# mrShark_06.net
KiCad netlist of a schematic drawn in EAGLE
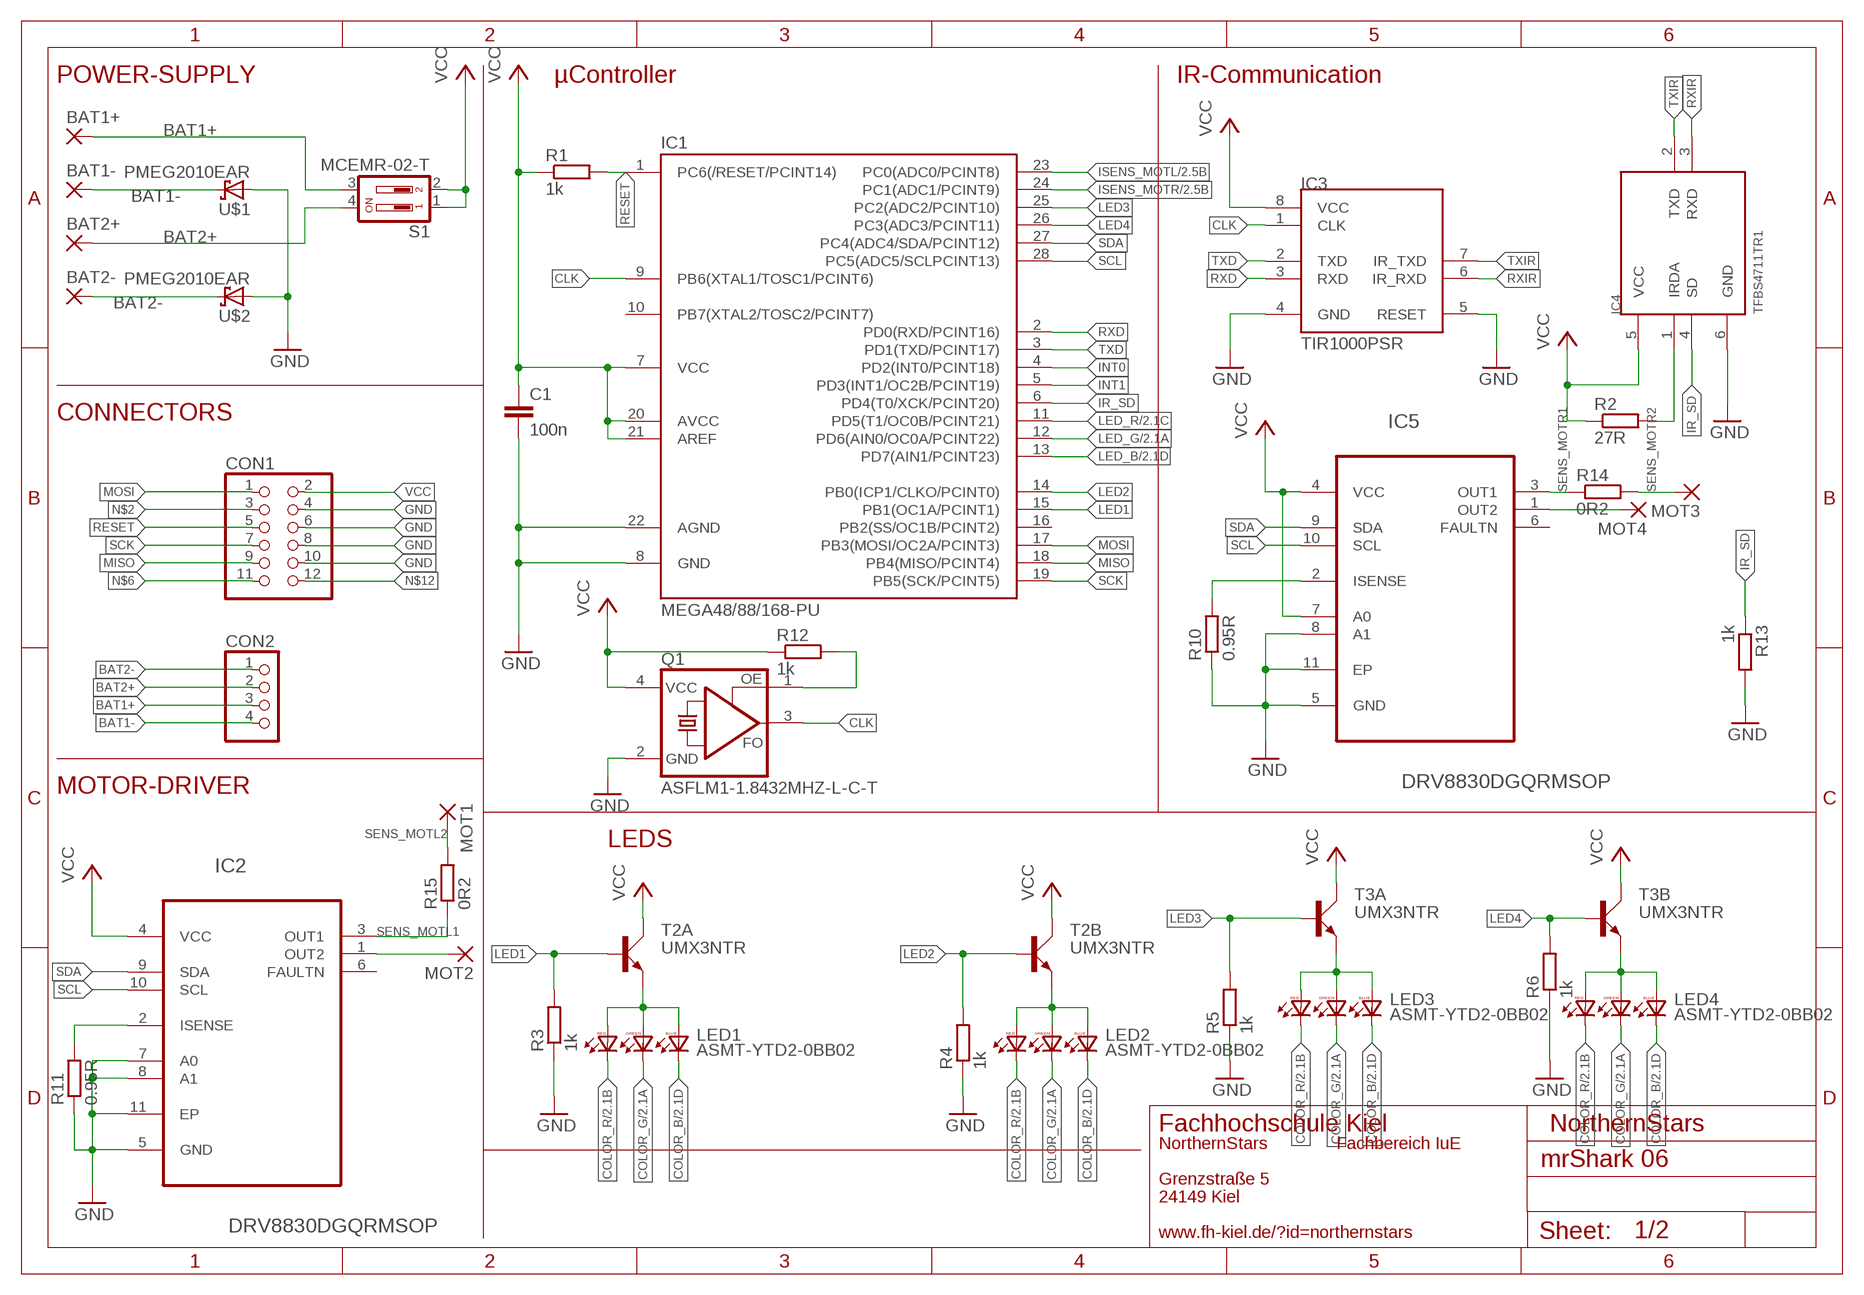
[diagram p0: schematic, sheet 1]
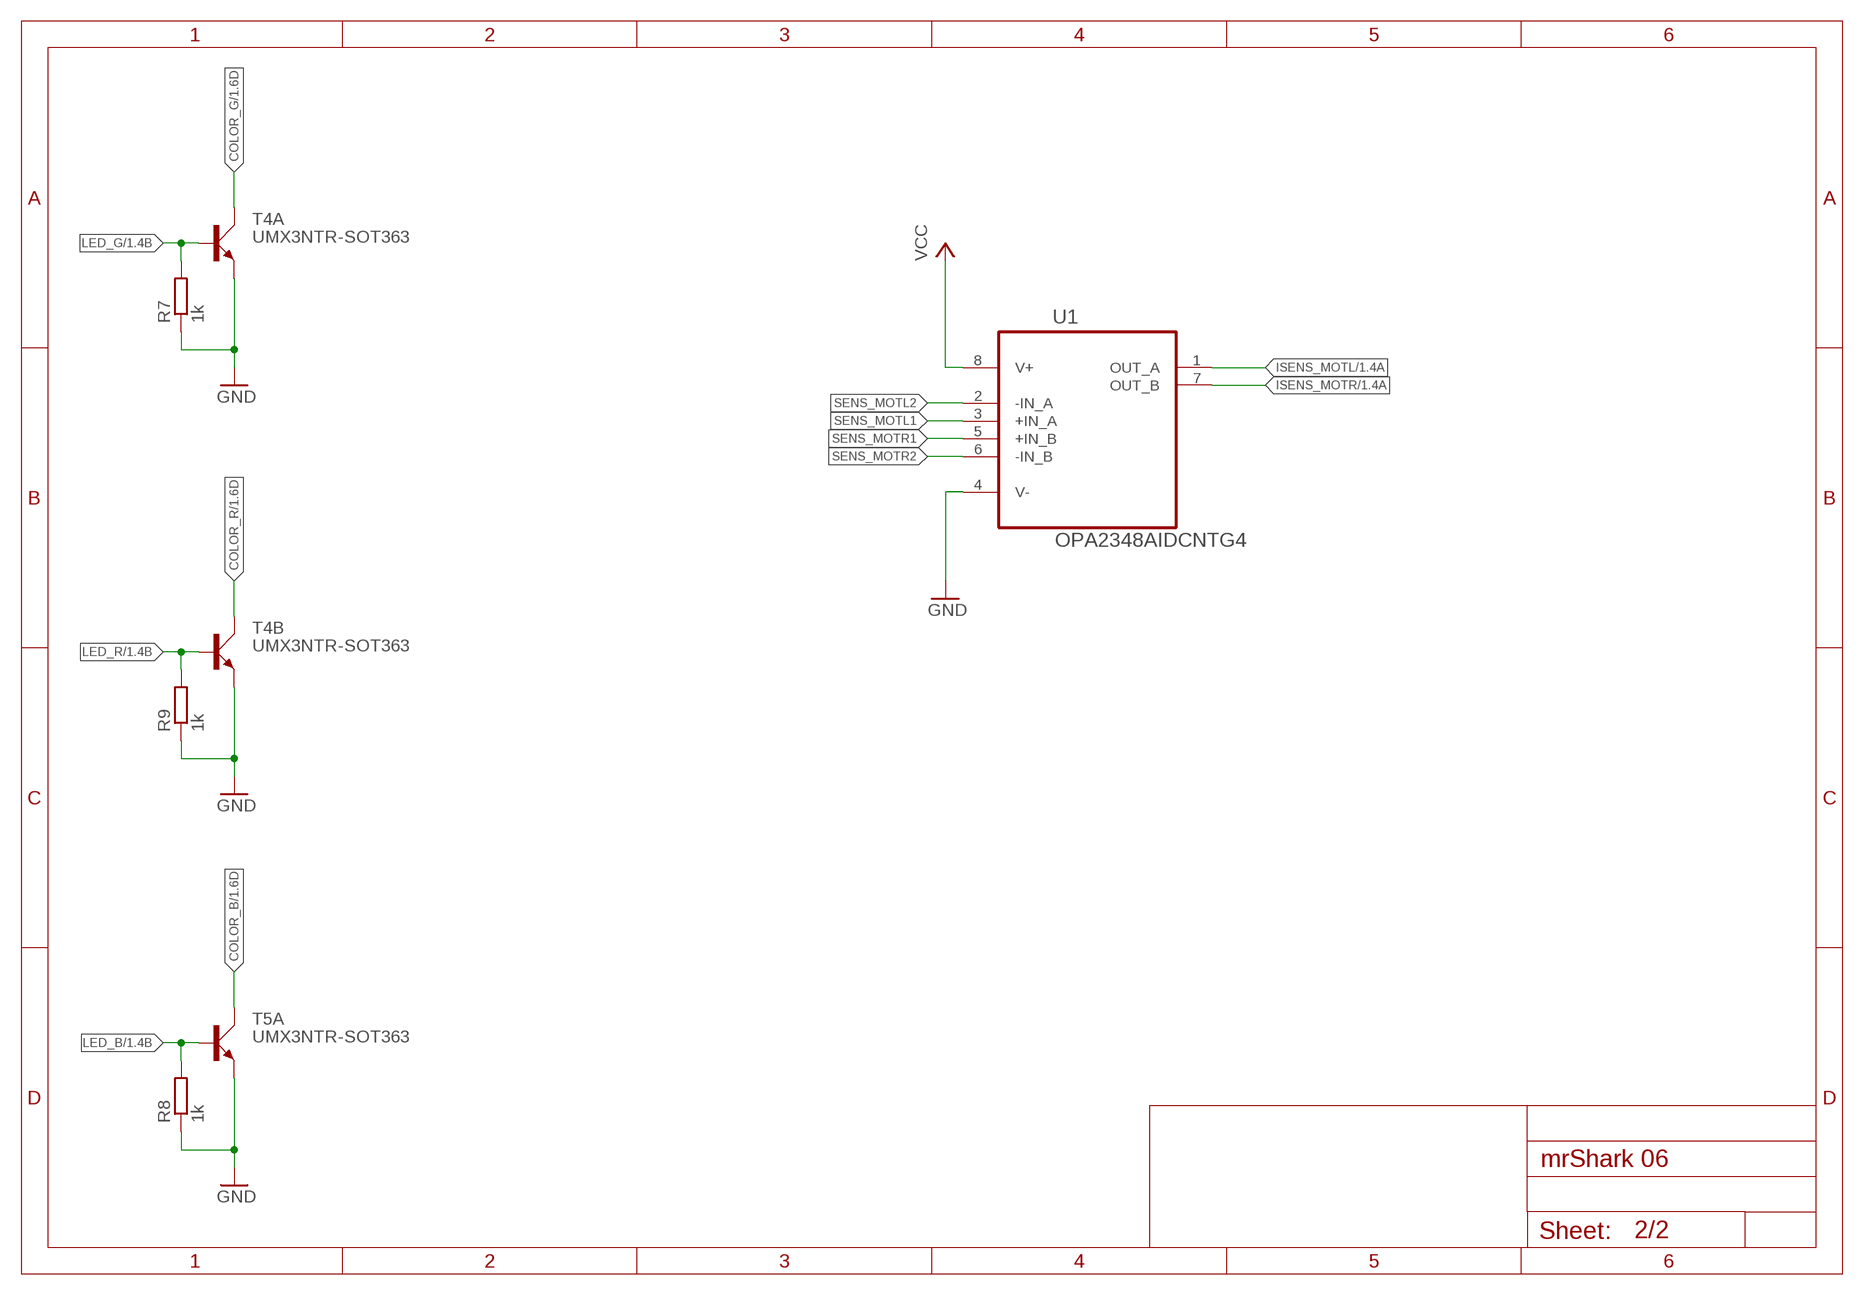
[diagram p1: schematic, sheet 2]

(export (version "E")
  (design (tool "Eeschema 10.0.6"))
  (components
    (comp (ref "R7")
      (value "1k")
      (footprint "eagle-import:R1206")
      (libsource (lib "eagle-import") (part "R-EU_R1206"))
    )
    (comp (ref "R8")
      (value "1k")
      (footprint "eagle-import:R1206")
      (libsource (lib "eagle-import") (part "R-EU_R1206"))
    )
    (comp (ref "R9")
      (value "1k")
      (footprint "eagle-import:R1206")
      (libsource (lib "eagle-import") (part "R-EU_R1206"))
    )
    (comp (ref "T4")
      (value "UMX3NTR-SOT363")
      (footprint "eagle-import:SOT363_INFINEON")
      (libsource (lib "eagle-import") (part "UMX3NTR-SOT363"))
    )
    (comp (ref "T5")
      (value "UMX3NTR-SOT363")
      (footprint "eagle-import:SOT363_INFINEON")
      (libsource (lib "eagle-import") (part "UMX3NTR-SOT363"))
    )
    (comp (ref "U1")
      (value "OPA2348AIDCNTG4")
      (footprint "eagle-import:SOT65P280X145-8N")
      (libsource (lib "eagle-import") (part "OPA2348AIDCNTG4"))
    )
    (comp (ref "BAT1+")
      (value "1,6/0,9")
      (footprint "eagle-import:1,6_0,9")
      (libsource (lib "eagle-import") (part "1,6/0,9"))
    )
    (comp (ref "BAT1-")
      (value "1,6/0,9")
      (footprint "eagle-import:1,6_0,9")
      (libsource (lib "eagle-import") (part "1,6/0,9"))
    )
    (comp (ref "BAT2+")
      (value "1,6/0,9")
      (footprint "eagle-import:1,6_0,9")
      (libsource (lib "eagle-import") (part "1,6/0,9"))
    )
    (comp (ref "BAT2-")
      (value "1,6/0,9")
      (footprint "eagle-import:1,6_0,9")
      (libsource (lib "eagle-import") (part "1,6/0,9"))
    )
    (comp (ref "C1")
      (value "100n")
      (footprint "eagle-import:C1206")
      (libsource (lib "eagle-import") (part "C-EUC1206"))
    )
    (comp (ref "CON1")
      (value "PINHD-2X06_2.54-SMD")
      (footprint "eagle-import:2X06SMD")
      (libsource (lib "eagle-import") (part "PINHD-2X06_2.54-SMD"))
    )
    (comp (ref "CON2")
      (value "PINHD-1X04_2.54-SMD-90°")
      (footprint "eagle-import:1X04SMD_90")
      (libsource (lib "eagle-import") (part "PINHD-1X04_2.54-SMD-90°"))
    )
    (comp (ref "IC1")
      (value "MEGA48/88/168-PU")
      (footprint "eagle-import:DIL28-3")
      (libsource (lib "eagle-import") (part "MEGA48/88/168-PU"))
    )
    (comp (ref "IC2")
      (value "DRV8830DGQRMSOP")
      (footprint "eagle-import:SOP65P640X110-15N")
      (fields (field (name "MPN") "DRV8830DGQR"))
      (libsource (lib "eagle-import") (part "DRV8830DGQRMSOP"))
    )
    (comp (ref "IC3")
      (value "TIR1000PSR")
      (footprint "eagle-import:SO-08")
      (libsource (lib "eagle-import") (part "TIR1000PSR"))
    )
    (comp (ref "IC4")
      (value "TFBS4711TR1")
      (footprint "eagle-import:TFBS4711")
      (libsource (lib "eagle-import") (part "TFBS4711TR1"))
    )
    (comp (ref "IC5")
      (value "DRV8830DGQRMSOP")
      (footprint "eagle-import:SOP65P640X110-15N")
      (fields (field (name "MPN") "DRV8830DGQR"))
      (libsource (lib "eagle-import") (part "DRV8830DGQRMSOP"))
    )
    (comp (ref "LED1")
      (value "ASMT-YTD2-0BB02")
      (footprint "eagle-import:PLCC6K")
      (libsource (lib "eagle-import") (part "PLCC6K"))
    )
    (comp (ref "LED2")
      (value "ASMT-YTD2-0BB02")
      (footprint "eagle-import:PLCC6K")
      (libsource (lib "eagle-import") (part "PLCC6K"))
    )
    (comp (ref "LED3")
      (value "ASMT-YTD2-0BB02")
      (footprint "eagle-import:PLCC6K")
      (libsource (lib "eagle-import") (part "PLCC6K"))
    )
    (comp (ref "LED4")
      (value "ASMT-YTD2-0BB02")
      (footprint "eagle-import:PLCC6K")
      (libsource (lib "eagle-import") (part "PLCC6K"))
    )
    (comp (ref "MOT1")
      (value "1,6/0,9")
      (footprint "eagle-import:1,6_0,9")
      (libsource (lib "eagle-import") (part "1,6/0,9"))
    )
    (comp (ref "MOT2")
      (value "1,6/0,9")
      (footprint "eagle-import:1,6_0,9")
      (libsource (lib "eagle-import") (part "1,6/0,9"))
    )
    (comp (ref "MOT3")
      (value "1,6/0,9")
      (footprint "eagle-import:1,6_0,9")
      (libsource (lib "eagle-import") (part "1,6/0,9"))
    )
    (comp (ref "MOT4")
      (value "1,6/0,9")
      (footprint "eagle-import:1,6_0,9")
      (libsource (lib "eagle-import") (part "1,6/0,9"))
    )
    (comp (ref "Q1")
      (value "ASFLM1-1.8432MHZ-L-C-T")
      (footprint "eagle-import:HC536")
      (libsource (lib "eagle-import") (part "HC536R"))
    )
    (comp (ref "R1")
      (value "1k")
      (footprint "eagle-import:R1206")
      (libsource (lib "eagle-import") (part "R-EU_R1206"))
    )
    (comp (ref "R2")
      (value "27R")
      (footprint "eagle-import:R1206")
      (libsource (lib "eagle-import") (part "R-EU_R1206"))
    )
    (comp (ref "R3")
      (value "1k")
      (footprint "eagle-import:R1206")
      (libsource (lib "eagle-import") (part "R-EU_R1206"))
    )
    (comp (ref "R4")
      (value "1k")
      (footprint "eagle-import:R1206")
      (libsource (lib "eagle-import") (part "R-EU_R1206"))
    )
    (comp (ref "R5")
      (value "1k")
      (footprint "eagle-import:R1206")
      (libsource (lib "eagle-import") (part "R-EU_R1206"))
    )
    (comp (ref "R6")
      (value "1k")
      (footprint "eagle-import:R1206")
      (libsource (lib "eagle-import") (part "R-EU_R1206"))
    )
    (comp (ref "R10")
      (value "0.95R")
      (footprint "eagle-import:R1206")
      (libsource (lib "eagle-import") (part "R-EU_R1206"))
    )
    (comp (ref "R11")
      (value "0.95R")
      (footprint "eagle-import:R1206")
      (libsource (lib "eagle-import") (part "R-EU_R1206"))
    )
    (comp (ref "R12")
      (value "1k")
      (footprint "eagle-import:R1206")
      (libsource (lib "eagle-import") (part "R-EU_R1206"))
    )
    (comp (ref "R13")
      (value "1k")
      (footprint "eagle-import:R1206")
      (libsource (lib "eagle-import") (part "R-EU_R1206"))
    )
    (comp (ref "R14")
      (value "0R2")
      (footprint "eagle-import:R0805")
      (libsource (lib "eagle-import") (part "R-EU_R0805"))
    )
    (comp (ref "R15")
      (value "0R2")
      (footprint "eagle-import:R0805")
      (libsource (lib "eagle-import") (part "R-EU_R0805"))
    )
    (comp (ref "S1")
      (value "MCEMR-02-T")
      (footprint "eagle-import:CTS-219-02")
      (libsource (lib "eagle-import") (part "219-02"))
    )
    (comp (ref "T2")
      (value "UMX3NTR")
      (footprint "eagle-import:SOT363_INFINEON")
      (libsource (lib "eagle-import") (part "UMX3NTR-SOT363"))
    )
    (comp (ref "T3")
      (value "UMX3NTR")
      (footprint "eagle-import:SOT363_INFINEON")
      (libsource (lib "eagle-import") (part "UMX3NTR-SOT363"))
    )
    (comp (ref "U$1")
      (value "PMEG2010EAR")
      (footprint "eagle-import:SOD323-R")
      (libsource (lib "eagle-import") (part "PMEG2010EAR"))
    )
    (comp (ref "U$2")
      (value "PMEG2010EAR")
      (footprint "eagle-import:SOD323-R")
      (libsource (lib "eagle-import") (part "PMEG2010EAR"))
    )
  )
  (nets
    (net (code "1") (name "BAT1+") (class "Default")
      (node (ref "BAT1+") (pin "1") (pinfunction "P_1") (pintype "passive"))
      (node (ref "CON2") (pin "3") (pinfunction "3_3") (pintype "passive"))
      (node (ref "S1") (pin "3") (pinfunction "3_3") (pintype "passive"))
    )
    (net (code "2") (name "BAT1-") (class "Default")
      (node (ref "BAT1-") (pin "1") (pinfunction "P_1") (pintype "passive"))
      (node (ref "CON2") (pin "4") (pinfunction "4_4") (pintype "passive"))
      (node (ref "U$1") (pin "C") (pinfunction "C_C") (pintype "passive"))
    )
    (net (code "3") (name "BAT2+") (class "Default")
      (node (ref "BAT2+") (pin "1") (pinfunction "P_1") (pintype "passive"))
      (node (ref "CON2") (pin "2") (pinfunction "2_2") (pintype "passive"))
      (node (ref "S1") (pin "4") (pinfunction "4_4") (pintype "passive"))
    )
    (net (code "4") (name "BAT2-") (class "Default")
      (node (ref "BAT2-") (pin "1") (pinfunction "P_1") (pintype "passive"))
      (node (ref "CON2") (pin "1") (pinfunction "1_1") (pintype "passive"))
      (node (ref "U$2") (pin "C") (pinfunction "C_C") (pintype "passive"))
    )
    (net (code "5") (name "CLK") (class "Default")
      (node (ref "IC1") (pin "9") (pinfunction "PB6(XTAL1/TOSC1/PCINT6)_9") (pintype "bidirectional"))
      (node (ref "IC3") (pin "1") (pinfunction "CLK_1") (pintype "bidirectional"))
      (node (ref "Q1") (pin "3") (pinfunction "FO_3") (pintype "output"))
    )
    (net (code "6") (name "COLOR_B") (class "Default")
      (node (ref "LED1") (pin "1") (pinfunction "BC_1") (pintype "passive"))
      (node (ref "LED2") (pin "1") (pinfunction "BC_1") (pintype "passive"))
      (node (ref "LED3") (pin "1") (pinfunction "BC_1") (pintype "passive"))
      (node (ref "LED4") (pin "1") (pinfunction "BC_1") (pintype "passive"))
      (node (ref "T5") (pin "6") (pinfunction "C_6") (pintype "passive"))
    )
    (net (code "7") (name "COLOR_G") (class "Default")
      (node (ref "LED1") (pin "2") (pinfunction "GC_2") (pintype "passive"))
      (node (ref "LED2") (pin "2") (pinfunction "GC_2") (pintype "passive"))
      (node (ref "LED3") (pin "2") (pinfunction "GC_2") (pintype "passive"))
      (node (ref "LED4") (pin "2") (pinfunction "GC_2") (pintype "passive"))
      (node (ref "T4") (pin "6") (pinfunction "C_6") (pintype "passive"))
    )
    (net (code "8") (name "COLOR_R") (class "Default")
      (node (ref "LED1") (pin "3") (pinfunction "RC_3") (pintype "passive"))
      (node (ref "LED2") (pin "3") (pinfunction "RC_3") (pintype "passive"))
      (node (ref "LED3") (pin "3") (pinfunction "RC_3") (pintype "passive"))
      (node (ref "LED4") (pin "3") (pinfunction "RC_3") (pintype "passive"))
      (node (ref "T4") (pin "4") (pinfunction "C_4") (pintype "passive"))
    )
    (net (code "9") (name "GND") (class "Default")
      (node (ref "C1") (pin "2") (pinfunction "2_2") (pintype "passive"))
      (node (ref "CON1") (pin "10") (pinfunction "10_10") (pintype "passive"))
      (node (ref "CON1") (pin "4") (pinfunction "4_4") (pintype "passive"))
      (node (ref "CON1") (pin "6") (pinfunction "6_6") (pintype "passive"))
      (node (ref "CON1") (pin "8") (pinfunction "8_8") (pintype "passive"))
      (node (ref "IC1") (pin "22") (pinfunction "AGND_22") (pintype "power_in"))
      (node (ref "IC1") (pin "8") (pinfunction "GND_8") (pintype "power_in"))
      (node (ref "IC2") (pin "11") (pinfunction "EP_11") (pintype "passive"))
      (node (ref "IC2") (pin "5") (pinfunction "GND_5") (pintype "passive"))
      (node (ref "IC2") (pin "7") (pinfunction "A0_7") (pintype "input"))
      (node (ref "IC2") (pin "8") (pinfunction "A1_8") (pintype "input"))
      (node (ref "IC3") (pin "4") (pinfunction "GND_4") (pintype "bidirectional"))
      (node (ref "IC3") (pin "5") (pinfunction "RESET_5") (pintype "bidirectional"))
      (node (ref "IC4") (pin "6") (pinfunction "GND_6") (pintype "bidirectional"))
      (node (ref "IC5") (pin "11") (pinfunction "EP_11") (pintype "passive"))
      (node (ref "IC5") (pin "5") (pinfunction "GND_5") (pintype "passive"))
      (node (ref "IC5") (pin "8") (pinfunction "A1_8") (pintype "input"))
      (node (ref "Q1") (pin "2") (pinfunction "GND_2") (pintype "power_in"))
      (node (ref "R10") (pin "1") (pinfunction "1_1") (pintype "passive"))
      (node (ref "R11") (pin "1") (pinfunction "1_1") (pintype "passive"))
      (node (ref "R13") (pin "2") (pinfunction "2_2") (pintype "passive"))
      (node (ref "R3") (pin "1") (pinfunction "1_1") (pintype "passive"))
      (node (ref "R4") (pin "1") (pinfunction "1_1") (pintype "passive"))
      (node (ref "R5") (pin "1") (pinfunction "1_1") (pintype "passive"))
      (node (ref "R6") (pin "1") (pinfunction "1_1") (pintype "passive"))
      (node (ref "R7") (pin "1") (pinfunction "1_1") (pintype "passive"))
      (node (ref "R8") (pin "1") (pinfunction "1_1") (pintype "passive"))
      (node (ref "R9") (pin "1") (pinfunction "1_1") (pintype "passive"))
      (node (ref "T4") (pin "1") (pinfunction "E_1") (pintype "passive"))
      (node (ref "T4") (pin "5") (pinfunction "E_5") (pintype "passive"))
      (node (ref "T5") (pin "1") (pinfunction "E_1") (pintype "passive"))
      (node (ref "U$1") (pin "A") (pinfunction "A_A") (pintype "passive"))
      (node (ref "U$2") (pin "A") (pinfunction "A_A") (pintype "passive"))
      (node (ref "U1") (pin "4") (pinfunction "V-_4") (pintype "power_in"))
    )
    (net (code "10") (name "INT0") (class "Default")
      (node (ref "IC1") (pin "4") (pinfunction "PD2(INT0/PCINT18)_4") (pintype "bidirectional"))
    )
    (net (code "11") (name "INT1") (class "Default")
      (node (ref "IC1") (pin "5") (pinfunction "PD3(INT1/OC2B/PCINT19)_5") (pintype "bidirectional"))
    )
    (net (code "12") (name "IR_SD") (class "Default")
      (node (ref "IC1") (pin "6") (pinfunction "PD4(T0/XCK/PCINT20)_6") (pintype "bidirectional"))
      (node (ref "IC4") (pin "4") (pinfunction "SD_4") (pintype "bidirectional"))
      (node (ref "R13") (pin "1") (pinfunction "1_1") (pintype "passive"))
    )
    (net (code "13") (name "ISENS_MOTL") (class "Default")
      (node (ref "IC1") (pin "23") (pinfunction "PC0(ADC0/PCINT8)_23") (pintype "bidirectional"))
      (node (ref "U1") (pin "1") (pinfunction "OUT_A_1") (pintype "output"))
    )
    (net (code "14") (name "ISENS_MOTR") (class "Default")
      (node (ref "IC1") (pin "24") (pinfunction "PC1(ADC1/PCINT9)_24") (pintype "bidirectional"))
      (node (ref "U1") (pin "7") (pinfunction "OUT_B_7") (pintype "output"))
    )
    (net (code "15") (name "LED1") (class "Default")
      (node (ref "IC1") (pin "15") (pinfunction "PB1(OC1A/PCINT1)_15") (pintype "bidirectional"))
      (node (ref "R3") (pin "2") (pinfunction "2_2") (pintype "passive"))
      (node (ref "T2") (pin "2") (pinfunction "B_2") (pintype "passive"))
    )
    (net (code "16") (name "LED2") (class "Default")
      (node (ref "IC1") (pin "14") (pinfunction "PB0(ICP1/CLKO/PCINT0)_14") (pintype "bidirectional"))
      (node (ref "R4") (pin "2") (pinfunction "2_2") (pintype "passive"))
      (node (ref "T2") (pin "3") (pinfunction "B_3") (pintype "passive"))
    )
    (net (code "17") (name "LED3") (class "Default")
      (node (ref "IC1") (pin "25") (pinfunction "PC2(ADC2/PCINT10)_25") (pintype "bidirectional"))
      (node (ref "R5") (pin "2") (pinfunction "2_2") (pintype "passive"))
      (node (ref "T3") (pin "2") (pinfunction "B_2") (pintype "passive"))
    )
    (net (code "18") (name "LED4") (class "Default")
      (node (ref "IC1") (pin "26") (pinfunction "PC3(ADC3/PCINT11)_26") (pintype "bidirectional"))
      (node (ref "R6") (pin "2") (pinfunction "2_2") (pintype "passive"))
      (node (ref "T3") (pin "3") (pinfunction "B_3") (pintype "passive"))
    )
    (net (code "19") (name "LED_B") (class "Default")
      (node (ref "IC1") (pin "13") (pinfunction "PD7(AIN1/PCINT23)_13") (pintype "bidirectional"))
      (node (ref "R8") (pin "2") (pinfunction "2_2") (pintype "passive"))
      (node (ref "T5") (pin "2") (pinfunction "B_2") (pintype "passive"))
    )
    (net (code "20") (name "LED_G") (class "Default")
      (node (ref "IC1") (pin "12") (pinfunction "PD6(AIN0/OC0A/PCINT22)_12") (pintype "bidirectional"))
      (node (ref "R7") (pin "2") (pinfunction "2_2") (pintype "passive"))
      (node (ref "T4") (pin "2") (pinfunction "B_2") (pintype "passive"))
    )
    (net (code "21") (name "LED_R") (class "Default")
      (node (ref "IC1") (pin "11") (pinfunction "PD5(T1/OC0B/PCINT21)_11") (pintype "bidirectional"))
      (node (ref "R9") (pin "2") (pinfunction "2_2") (pintype "passive"))
      (node (ref "T4") (pin "3") (pinfunction "B_3") (pintype "passive"))
    )
    (net (code "22") (name "MISO") (class "Default")
      (node (ref "CON1") (pin "9") (pinfunction "9_9") (pintype "passive"))
      (node (ref "IC1") (pin "18") (pinfunction "PB4(MISO/PCINT4)_18") (pintype "bidirectional"))
    )
    (net (code "23") (name "MOSI") (class "Default")
      (node (ref "CON1") (pin "1") (pinfunction "1_1") (pintype "passive"))
      (node (ref "IC1") (pin "17") (pinfunction "PB3(MOSI/OC2A/PCINT3)_17") (pintype "bidirectional"))
    )
    (net (code "24") (name "N$2") (class "Default")
      (node (ref "CON1") (pin "3") (pinfunction "3_3") (pintype "passive"))
    )
    (net (code "25") (name "N$6") (class "Default")
      (node (ref "CON1") (pin "11") (pinfunction "11_11") (pintype "passive"))
    )
    (net (code "26") (name "N$12") (class "Default")
      (node (ref "CON1") (pin "12") (pinfunction "12_12") (pintype "passive"))
    )
    (net (code "27") (name "Net-(IC2-ISENSE)") (class "Default")
      (node (ref "IC2") (pin "2") (pinfunction "ISENSE_2") (pintype "input"))
      (node (ref "R11") (pin "2") (pinfunction "2_2") (pintype "passive"))
    )
    (net (code "28") (name "Net-(IC2-OUT2)") (class "Default")
      (node (ref "IC2") (pin "1") (pinfunction "OUT2_1") (pintype "output"))
      (node (ref "MOT2") (pin "1") (pinfunction "P_1") (pintype "passive"))
    )
    (net (code "29") (name "Net-(IC4-IRDA)") (class "Default")
      (node (ref "IC4") (pin "1") (pinfunction "IRDA_1") (pintype "bidirectional"))
      (node (ref "R2") (pin "2") (pinfunction "2_2") (pintype "passive"))
    )
    (net (code "30") (name "Net-(IC5-ISENSE)") (class "Default")
      (node (ref "IC5") (pin "2") (pinfunction "ISENSE_2") (pintype "input"))
      (node (ref "R10") (pin "2") (pinfunction "2_2") (pintype "passive"))
    )
    (net (code "31") (name "Net-(IC5-OUT2)") (class "Default")
      (node (ref "IC5") (pin "1") (pinfunction "OUT2_1") (pintype "output"))
      (node (ref "MOT4") (pin "1") (pinfunction "P_1") (pintype "passive"))
    )
    (net (code "32") (name "Net-(LED1-BA)") (class "Default")
      (node (ref "LED1") (pin "4") (pinfunction "RA_4") (pintype "passive"))
      (node (ref "LED1") (pin "5") (pinfunction "GA_5") (pintype "passive"))
      (node (ref "LED1") (pin "6") (pinfunction "BA_6") (pintype "passive"))
      (node (ref "T2") (pin "1") (pinfunction "E_1") (pintype "passive"))
    )
    (net (code "33") (name "Net-(LED2-BA)") (class "Default")
      (node (ref "LED2") (pin "4") (pinfunction "RA_4") (pintype "passive"))
      (node (ref "LED2") (pin "5") (pinfunction "GA_5") (pintype "passive"))
      (node (ref "LED2") (pin "6") (pinfunction "BA_6") (pintype "passive"))
      (node (ref "T2") (pin "5") (pinfunction "E_5") (pintype "passive"))
    )
    (net (code "34") (name "Net-(LED3-BA)") (class "Default")
      (node (ref "LED3") (pin "4") (pinfunction "RA_4") (pintype "passive"))
      (node (ref "LED3") (pin "5") (pinfunction "GA_5") (pintype "passive"))
      (node (ref "LED3") (pin "6") (pinfunction "BA_6") (pintype "passive"))
      (node (ref "T3") (pin "1") (pinfunction "E_1") (pintype "passive"))
    )
    (net (code "35") (name "Net-(LED4-BA)") (class "Default")
      (node (ref "LED4") (pin "4") (pinfunction "RA_4") (pintype "passive"))
      (node (ref "LED4") (pin "5") (pinfunction "GA_5") (pintype "passive"))
      (node (ref "LED4") (pin "6") (pinfunction "BA_6") (pintype "passive"))
      (node (ref "T3") (pin "5") (pinfunction "E_5") (pintype "passive"))
    )
    (net (code "36") (name "Net-(Q1-OE)") (class "Default")
      (node (ref "Q1") (pin "1") (pinfunction "OE_1") (pintype "input"))
      (node (ref "R12") (pin "2") (pinfunction "2_2") (pintype "passive"))
    )
    (net (code "37") (name "RESET") (class "Default")
      (node (ref "CON1") (pin "5") (pinfunction "5_5") (pintype "passive"))
      (node (ref "IC1") (pin "1") (pinfunction "PC6(/RESET/PCINT14)_1") (pintype "bidirectional"))
      (node (ref "R1") (pin "2") (pinfunction "2_2") (pintype "passive"))
    )
    (net (code "38") (name "RXD") (class "Default")
      (node (ref "IC1") (pin "2") (pinfunction "PD0(RXD/PCINT16)_2") (pintype "bidirectional"))
      (node (ref "IC3") (pin "3") (pinfunction "RXD_3") (pintype "bidirectional"))
    )
    (net (code "39") (name "RXIR") (class "Default")
      (node (ref "IC3") (pin "6") (pinfunction "IR_RXD_6") (pintype "bidirectional"))
      (node (ref "IC4") (pin "3") (pinfunction "RXD_3") (pintype "output"))
    )
    (net (code "40") (name "SCK") (class "Default")
      (node (ref "CON1") (pin "7") (pinfunction "7_7") (pintype "passive"))
      (node (ref "IC1") (pin "19") (pinfunction "PB5(SCK/PCINT5)_19") (pintype "bidirectional"))
    )
    (net (code "41") (name "SCL") (class "Default")
      (node (ref "IC1") (pin "28") (pinfunction "PC5(ADC5/SCLPCINT13)_28") (pintype "bidirectional"))
      (node (ref "IC2") (pin "10") (pinfunction "SCL_10") (pintype "input"))
      (node (ref "IC5") (pin "10") (pinfunction "SCL_10") (pintype "input"))
    )
    (net (code "42") (name "SDA") (class "Default")
      (node (ref "IC1") (pin "27") (pinfunction "PC4(ADC4/SDA/PCINT12)_27") (pintype "bidirectional"))
      (node (ref "IC2") (pin "9") (pinfunction "SDA_9") (pintype "bidirectional"))
      (node (ref "IC5") (pin "9") (pinfunction "SDA_9") (pintype "bidirectional"))
    )
    (net (code "43") (name "SENS_MOTL1") (class "Default")
      (node (ref "IC2") (pin "3") (pinfunction "OUT1_3") (pintype "output"))
      (node (ref "R15") (pin "1") (pinfunction "1_1") (pintype "passive"))
      (node (ref "U1") (pin "3") (pinfunction "+IN_A_3") (pintype "input"))
    )
    (net (code "44") (name "SENS_MOTL2") (class "Default")
      (node (ref "MOT1") (pin "1") (pinfunction "P_1") (pintype "passive"))
      (node (ref "R15") (pin "2") (pinfunction "2_2") (pintype "passive"))
      (node (ref "U1") (pin "2") (pinfunction "-IN_A_2") (pintype "input"))
    )
    (net (code "45") (name "SENS_MOTR1") (class "Default")
      (node (ref "IC5") (pin "3") (pinfunction "OUT1_3") (pintype "output"))
      (node (ref "R14") (pin "1") (pinfunction "1_1") (pintype "passive"))
      (node (ref "U1") (pin "5") (pinfunction "+IN_B_5") (pintype "input"))
    )
    (net (code "46") (name "SENS_MOTR2") (class "Default")
      (node (ref "MOT3") (pin "1") (pinfunction "P_1") (pintype "passive"))
      (node (ref "R14") (pin "2") (pinfunction "2_2") (pintype "passive"))
      (node (ref "U1") (pin "6") (pinfunction "-IN_B_6") (pintype "input"))
    )
    (net (code "47") (name "TXD") (class "Default")
      (node (ref "IC1") (pin "3") (pinfunction "PD1(TXD/PCINT17)_3") (pintype "bidirectional"))
      (node (ref "IC3") (pin "2") (pinfunction "TXD_2") (pintype "bidirectional"))
    )
    (net (code "48") (name "TXIR") (class "Default")
      (node (ref "IC3") (pin "7") (pinfunction "IR_TXD_7") (pintype "bidirectional"))
      (node (ref "IC4") (pin "2") (pinfunction "TXD_2") (pintype "input"))
    )
    (net (code "49") (name "VCC") (class "Default")
      (node (ref "C1") (pin "1") (pinfunction "1_1") (pintype "passive"))
      (node (ref "CON1") (pin "2") (pinfunction "2_2") (pintype "passive"))
      (node (ref "IC1") (pin "20") (pinfunction "AVCC_20") (pintype "passive"))
      (node (ref "IC1") (pin "21") (pinfunction "AREF_21") (pintype "passive"))
      (node (ref "IC1") (pin "7") (pinfunction "VCC_7") (pintype "power_in"))
      (node (ref "IC2") (pin "4") (pinfunction "VCC_4") (pintype "power_in"))
      (node (ref "IC3") (pin "8") (pinfunction "VCC_8") (pintype "bidirectional"))
      (node (ref "IC4") (pin "5") (pinfunction "VCC_5") (pintype "power_in"))
      (node (ref "IC5") (pin "4") (pinfunction "VCC_4") (pintype "power_in"))
      (node (ref "IC5") (pin "7") (pinfunction "A0_7") (pintype "input"))
      (node (ref "Q1") (pin "4") (pinfunction "VCC_4") (pintype "power_in"))
      (node (ref "R1") (pin "1") (pinfunction "1_1") (pintype "passive"))
      (node (ref "R12") (pin "1") (pinfunction "1_1") (pintype "passive"))
      (node (ref "R2") (pin "1") (pinfunction "1_1") (pintype "passive"))
      (node (ref "S1") (pin "1") (pinfunction "1_1") (pintype "passive"))
      (node (ref "S1") (pin "2") (pinfunction "2_2") (pintype "passive"))
      (node (ref "T2") (pin "4") (pinfunction "C_4") (pintype "passive"))
      (node (ref "T2") (pin "6") (pinfunction "C_6") (pintype "passive"))
      (node (ref "T3") (pin "4") (pinfunction "C_4") (pintype "passive"))
      (node (ref "T3") (pin "6") (pinfunction "C_6") (pintype "passive"))
      (node (ref "U1") (pin "8") (pinfunction "V+_8") (pintype "power_in"))
    )
    (net (code "50") (name "unconnected-(IC1-PB2(SS{slash}OC1B{slash}PCINT2)-Pad16)") (class "Default")
      (node (ref "IC1") (pin "16") (pinfunction "PB2(SS/OC1B/PCINT2)_16") (pintype "bidirectional"))
    )
    (net (code "51") (name "unconnected-(IC1-PB7(XTAL2{slash}TOSC2{slash}PCINT7)-Pad10)") (class "Default")
      (node (ref "IC1") (pin "10") (pinfunction "PB7(XTAL2/TOSC2/PCINT7)_10") (pintype "bidirectional"))
    )
    (net (code "52") (name "unconnected-(IC2-FAULTN-Pad6)") (class "Default")
      (node (ref "IC2") (pin "6") (pinfunction "FAULTN_6") (pintype "output"))
    )
    (net (code "53") (name "unconnected-(IC5-FAULTN-Pad6)") (class "Default")
      (node (ref "IC5") (pin "6") (pinfunction "FAULTN_6") (pintype "output"))
    )
  )
)
